# uCurrent.net
KiCad netlist of a schematic drawn in EAGLE
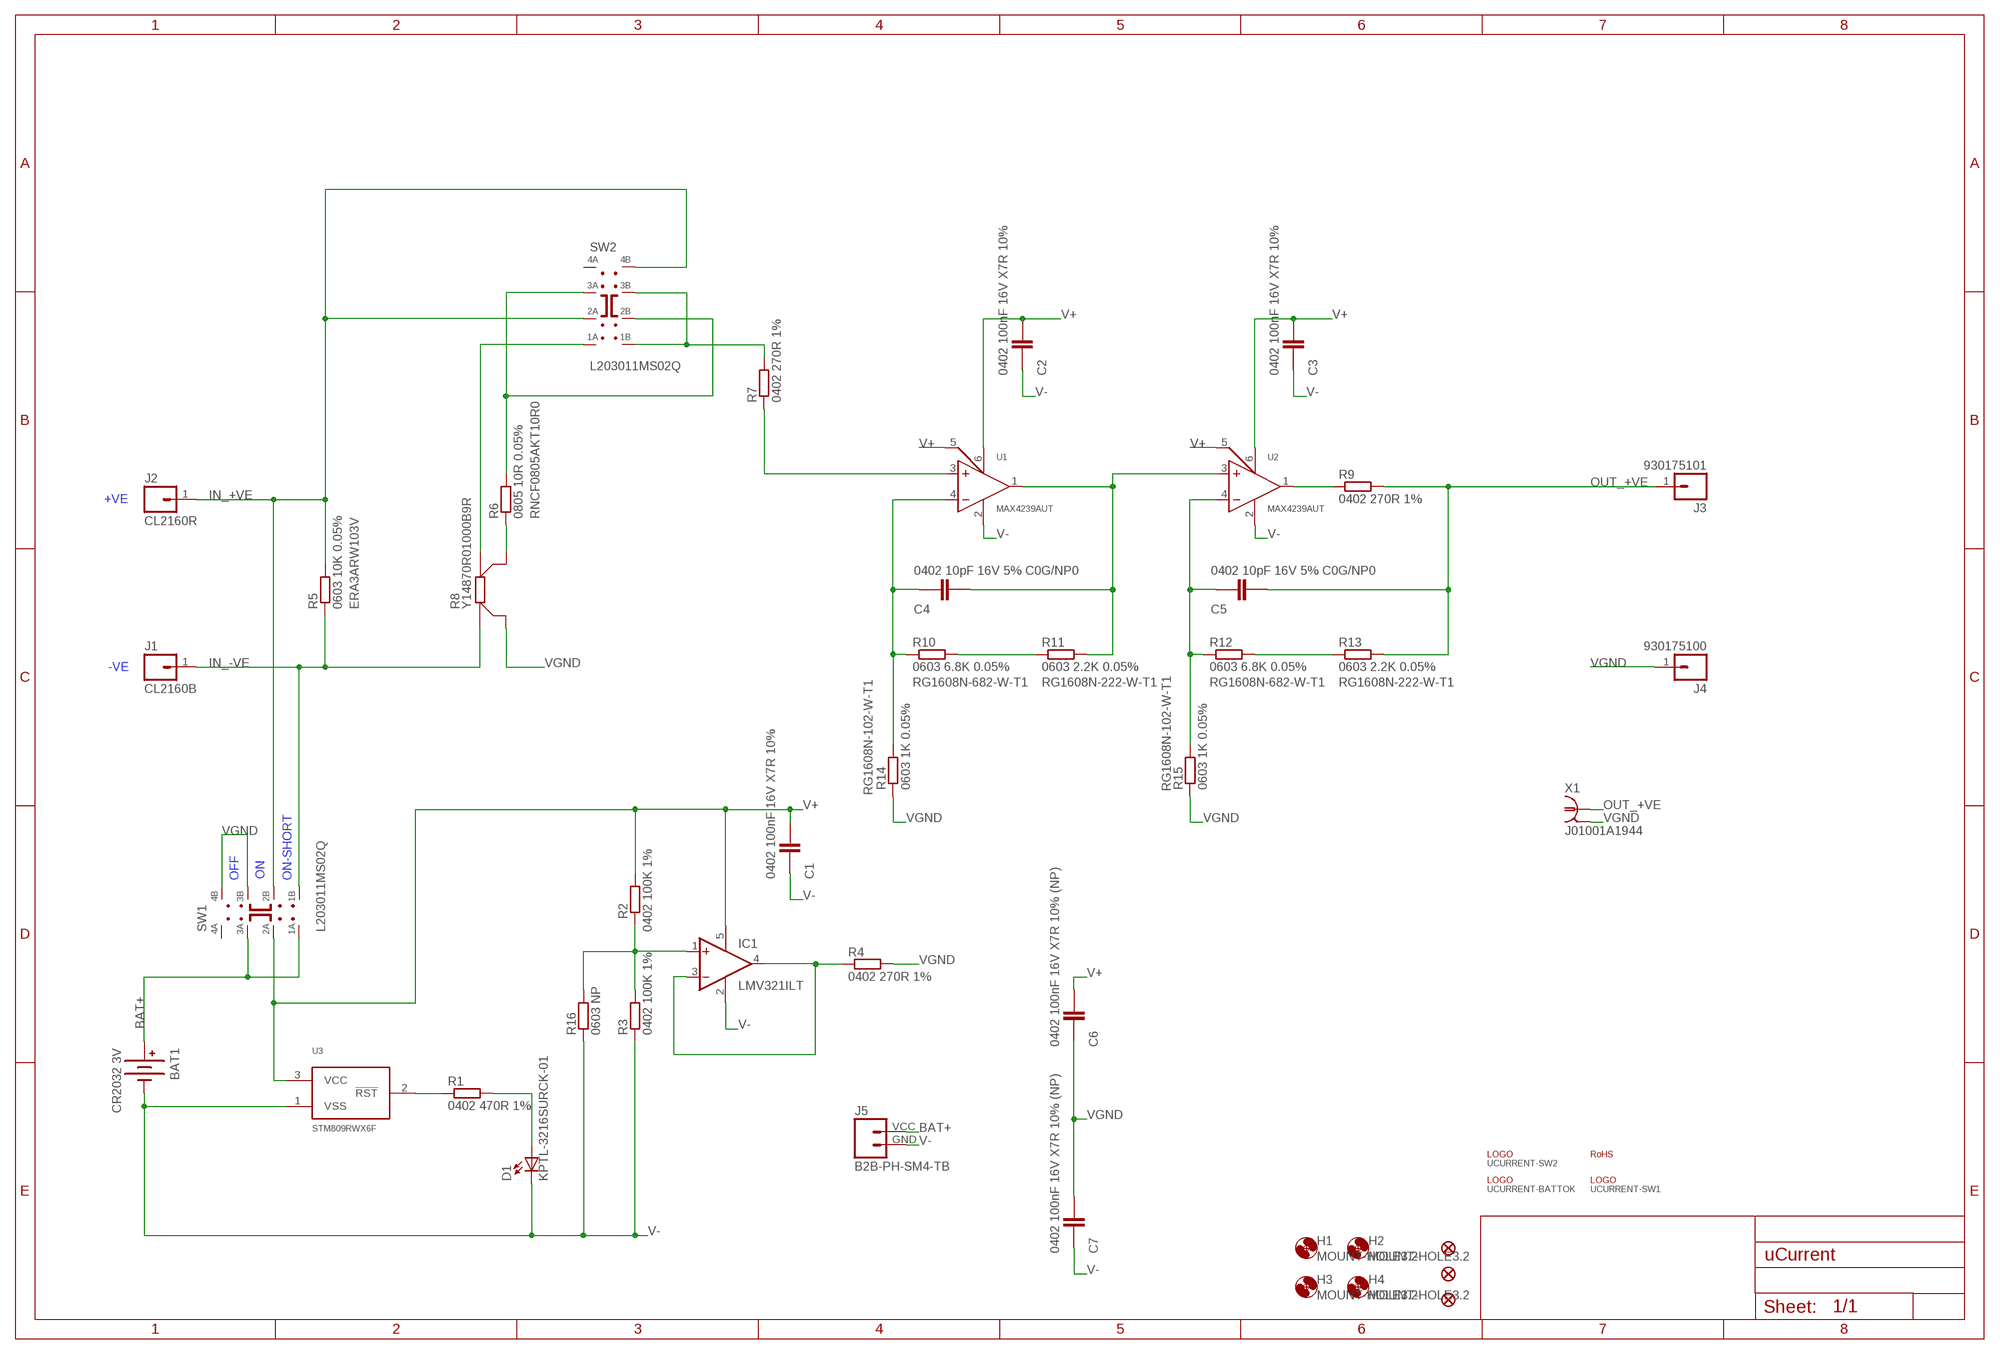
[diagram p0: schematic, sheet 1]

(export (version "E")
  (design (tool "Eeschema 10.0.6"))
  (components
    (comp (ref "BAT1")
      (value "CR2032 3V")
      (footprint "eagle-import:KEYSTONE_1058")
      (libsource (lib "eagle-import") (part "BATTERY-KEYSTONE_1058"))
    )
    (comp (ref "C1")
      (value "0402 100nF 16V X7R 10%")
      (footprint "eagle-import:C0402-SMALLER")
      (libsource (lib "eagle-import") (part "C-EUC0402-SMALLER"))
    )
    (comp (ref "C2")
      (value "0402 100nF 16V X7R 10%")
      (footprint "eagle-import:C0402-SMALLER")
      (libsource (lib "eagle-import") (part "C-EUC0402-SMALLER"))
    )
    (comp (ref "C3")
      (value "0402 100nF 16V X7R 10%")
      (footprint "eagle-import:C0402-SMALLER")
      (libsource (lib "eagle-import") (part "C-EUC0402-SMALLER"))
    )
    (comp (ref "C4")
      (value "0402 10pF 16V 5% C0G/NP0")
      (footprint "eagle-import:C0402-SMALLER")
      (libsource (lib "eagle-import") (part "C-EUC0402-SMALLER"))
    )
    (comp (ref "C5")
      (value "0402 10pF 16V 5% C0G/NP0")
      (footprint "eagle-import:C0402-SMALLER")
      (libsource (lib "eagle-import") (part "C-EUC0402-SMALLER"))
    )
    (comp (ref "C6")
      (value "0402 100nF 16V X7R 10% (NP)")
      (footprint "eagle-import:C0402-SMALLER")
      (libsource (lib "eagle-import") (part "C-EUC0402-SMALLER"))
    )
    (comp (ref "C7")
      (value "0402 100nF 16V X7R 10% (NP)")
      (footprint "eagle-import:C0402-SMALLER")
      (libsource (lib "eagle-import") (part "C-EUC0402-SMALLER"))
    )
    (comp (ref "D1")
      (value "KPTL-3216SURCK-01")
      (footprint "eagle-import:KPTL-3216")
      (libsource (lib "eagle-import") (part "LED-KPTL-3216"))
    )
    (comp (ref "H1")
      (value "MOUNT-HOLE3.2")
      (footprint "eagle-import:3,2")
      (libsource (lib "eagle-import") (part "MOUNT-HOLE3.2"))
    )
    (comp (ref "H2")
      (value "MOUNT-HOLE3.2")
      (footprint "eagle-import:3,2")
      (libsource (lib "eagle-import") (part "MOUNT-HOLE3.2"))
    )
    (comp (ref "H3")
      (value "MOUNT-HOLE3.2")
      (footprint "eagle-import:3,2")
      (libsource (lib "eagle-import") (part "MOUNT-HOLE3.2"))
    )
    (comp (ref "H4")
      (value "MOUNT-HOLE3.2")
      (footprint "eagle-import:3,2")
      (libsource (lib "eagle-import") (part "MOUNT-HOLE3.2"))
    )
    (comp (ref "IC1")
      (value "LMV321ILT")
      (footprint "eagle-import:SOT23-5")
      (libsource (lib "eagle-import") (part "LMV321?M5X"))
    )
    (comp (ref "J1")
      (value "CL2160B")
      (footprint "eagle-import:CL2160R")
      (libsource (lib "eagle-import") (part "M01-CL2160R"))
    )
    (comp (ref "J2")
      (value "CL2160R")
      (footprint "eagle-import:CL2160R")
      (libsource (lib "eagle-import") (part "M01-CL2160R"))
    )
    (comp (ref "J3")
      (value "930175101")
      (footprint "eagle-import:BUG10_SOCKET")
      (libsource (lib "eagle-import") (part "M01-BUG10"))
    )
    (comp (ref "J4")
      (value "930175100")
      (footprint "eagle-import:BUG10_SOCKET")
      (libsource (lib "eagle-import") (part "M01-BUG10"))
    )
    (comp (ref "J5")
      (value "B2B-PH-SM4-TB")
      (footprint "eagle-import:JST-PH-SMD-VERT-02")
      (libsource (lib "eagle-import") (part "M02-JST-PH-SMD-VERT"))
    )
    (comp (ref "JP1")
      (value "FIDUCIAL1X2.5-STOP")
      (footprint "eagle-import:FIDUCIAL-1X2.5-STOP")
      (libsource (lib "eagle-import") (part "FIDUCIAL1X2.5-STOP"))
    )
    (comp (ref "JP2")
      (value "FIDUCIAL1X2.5-STOP")
      (footprint "eagle-import:FIDUCIAL-1X2.5-STOP")
      (libsource (lib "eagle-import") (part "FIDUCIAL1X2.5-STOP"))
    )
    (comp (ref "JP3")
      (value "FIDUCIAL1X2.5-STOP")
      (footprint "eagle-import:FIDUCIAL-1X2.5-STOP")
      (libsource (lib "eagle-import") (part "FIDUCIAL1X2.5-STOP"))
    )
    (comp (ref "L1")
      (value "UCURRENT-BATTOK")
      (footprint "eagle-import:UCURRENT_BATTOK")
      (libsource (lib "eagle-import") (part "UCURRENT-BATTOK"))
    )
    (comp (ref "L2")
      (value "UCURRENT-SW1")
      (footprint "eagle-import:UCURRENT_SW1")
      (libsource (lib "eagle-import") (part "UCURRENT-SW1"))
    )
    (comp (ref "L3")
      (value "UCURRENT-SW2")
      (footprint "eagle-import:UCURRENT_SW2")
      (libsource (lib "eagle-import") (part "UCURRENT-SW2"))
    )
    (comp (ref "R1")
      (value "0402 470R 1%")
      (footprint "eagle-import:R0402-SMALLER")
      (libsource (lib "eagle-import") (part "R-EU_R0402-SMALLER"))
    )
    (comp (ref "R2")
      (value "0402 100K 1%")
      (footprint "eagle-import:R0402-SMALLER")
      (libsource (lib "eagle-import") (part "R-EU_R0402-SMALLER"))
    )
    (comp (ref "R3")
      (value "0402 100K 1%")
      (footprint "eagle-import:R0402-SMALLER")
      (libsource (lib "eagle-import") (part "R-EU_R0402-SMALLER"))
    )
    (comp (ref "R4")
      (value "0402 270R 1%")
      (footprint "eagle-import:R0402-SMALLER")
      (libsource (lib "eagle-import") (part "R-EU_R0402-SMALLER"))
    )
    (comp (ref "R5")
      (value "0603 10K 0.05%")
      (footprint "eagle-import:C0603K-SMALL")
      (fields (field (name "MPN") "ERA3ARW103V"))
      (libsource (lib "eagle-import") (part "R-EU_0603K-SMALL"))
    )
    (comp (ref "R6")
      (value "0805 10R 0.05%")
      (footprint "eagle-import:R0805")
      (fields (field (name "MPN") "RNCF0805AKT10R0"))
      (libsource (lib "eagle-import") (part "R-EU_R0805"))
    )
    (comp (ref "R7")
      (value "0402 270R 1%")
      (footprint "eagle-import:R0402-SMALLER")
      (libsource (lib "eagle-import") (part "R-EU_R0402-SMALLER"))
    )
    (comp (ref "R8")
      (value "Y14870R01000B9R")
      (footprint "eagle-import:CSM2512-L")
      (libsource (lib "eagle-import") (part "R-EU_KELVIN_Y14870R01000B9R"))
    )
    (comp (ref "R9")
      (value "0402 270R 1%")
      (footprint "eagle-import:R0402-SMALLER")
      (libsource (lib "eagle-import") (part "R-EU_R0402-SMALLER"))
    )
    (comp (ref "R10")
      (value "0603 6.8K 0.05%")
      (footprint "eagle-import:C0603K-SMALL")
      (fields (field (name "MPN") "RG1608N-682-W-T1"))
      (libsource (lib "eagle-import") (part "R-EU_0603K-SMALL"))
    )
    (comp (ref "R11")
      (value "0603 2.2K 0.05%")
      (footprint "eagle-import:C0603K-SMALL")
      (fields (field (name "MPN") "RG1608N-222-W-T1"))
      (libsource (lib "eagle-import") (part "R-EU_0603K-SMALL"))
    )
    (comp (ref "R12")
      (value "0603 6.8K 0.05%")
      (footprint "eagle-import:C0603K-SMALL")
      (fields (field (name "MPN") "RG1608N-682-W-T1"))
      (libsource (lib "eagle-import") (part "R-EU_0603K-SMALL"))
    )
    (comp (ref "R13")
      (value "0603 2.2K 0.05%")
      (footprint "eagle-import:C0603K-SMALL")
      (fields (field (name "MPN") "RG1608N-222-W-T1"))
      (libsource (lib "eagle-import") (part "R-EU_0603K-SMALL"))
    )
    (comp (ref "R14")
      (value "0603 1K 0.05%")
      (footprint "eagle-import:C0603K-SMALL")
      (fields (field (name "MPN") "RG1608N-102-W-T1"))
      (libsource (lib "eagle-import") (part "R-EU_0603K-SMALL"))
    )
    (comp (ref "R15")
      (value "0603 1K 0.05%")
      (footprint "eagle-import:C0603K-SMALL")
      (fields (field (name "MPN") "RG1608N-102-W-T1"))
      (libsource (lib "eagle-import") (part "R-EU_0603K-SMALL"))
    )
    (comp (ref "R16")
      (value "0603 NP")
      (footprint "eagle-import:C0603K-SMALL")
      (libsource (lib "eagle-import") (part "R-EU_0603K-SMALL"))
    )
    (comp (ref "SW1")
      (value "L203011MS02Q")
      (footprint "eagle-import:L203011MS02Q")
      (libsource (lib "eagle-import") (part "SWITCH-DP3T-L203011MS02Q"))
    )
    (comp (ref "SW2")
      (value "L203011MS02Q")
      (footprint "eagle-import:L203011MS02Q")
      (libsource (lib "eagle-import") (part "SWITCH-DP3T-L203011MS02Q"))
    )
    (comp (ref "U$1")
      (value "ROHS-1MM")
      (footprint "eagle-import:ROHS-1MM")
      (libsource (lib "eagle-import") (part "ROHS-1MM"))
    )
    (comp (ref "U1")
      (value "MAX4239AUT")
      (footprint "eagle-import:SOT-23-6")
      (libsource (lib "eagle-import") (part "MAX4239"))
    )
    (comp (ref "U2")
      (value "MAX4239AUT")
      (footprint "eagle-import:SOT-23-6")
      (libsource (lib "eagle-import") (part "MAX4239"))
    )
    (comp (ref "U3")
      (value "STM809RWX6F")
      (footprint "eagle-import:SOT23-3")
      (libsource (lib "eagle-import") (part "STM809RWX6F"))
    )
    (comp (ref "X1")
      (value "J01001A1944")
      (footprint "eagle-import:J01001A1944")
      (libsource (lib "eagle-import") (part "BNC_J01001A1944"))
    )
  )
  (nets
    (net (code "1") (name "/BAT+") (class "Default")
      (node (ref "BAT1") (pin "+VE") (pinfunction "+_+VE") (pintype "power_in"))
      (node (ref "J5") (pin "VCC") (pinfunction "2_VCC") (pintype "passive"))
      (node (ref "SW1") (pin "1") (pinfunction "1_1") (pintype "bidirectional"))
      (node (ref "SW1") (pin "3") (pinfunction "3_3") (pintype "bidirectional"))
    )
    (net (code "2") (name "/IN_+VE") (class "Default")
      (node (ref "J2") (pin "1") (pinfunction "1_1") (pintype "passive"))
      (node (ref "R5") (pin "2") (pinfunction "2_2") (pintype "passive"))
      (node (ref "SW1") (pin "6") (pinfunction "6_6") (pintype "bidirectional"))
      (node (ref "SW2") (pin "2") (pinfunction "2_2") (pintype "bidirectional"))
      (node (ref "SW2") (pin "8") (pinfunction "8_8") (pintype "bidirectional"))
    )
    (net (code "3") (name "/IN_-VE") (class "Default")
      (node (ref "J1") (pin "1") (pinfunction "1_1") (pintype "passive"))
      (node (ref "R5") (pin "1") (pinfunction "1_1") (pintype "passive"))
      (node (ref "R8") (pin "I1") (pinfunction "A_I1") (pintype "passive"))
      (node (ref "SW1") (pin "5") (pinfunction "5_5") (pintype "bidirectional"))
    )
    (net (code "4") (name "/OUT_+VE") (class "Default")
      (node (ref "C5") (pin "1") (pinfunction "1_1") (pintype "passive"))
      (node (ref "J3") (pin "1") (pinfunction "1_1") (pintype "passive"))
      (node (ref "R13") (pin "2") (pinfunction "2_2") (pintype "passive"))
      (node (ref "R9") (pin "2") (pinfunction "2_2") (pintype "passive"))
      (node (ref "X1") (pin "1") (pinfunction "1_1") (pintype "passive"))
    )
    (net (code "5") (name "/V+") (class "Default")
      (node (ref "C1") (pin "1") (pinfunction "1_1") (pintype "passive"))
      (node (ref "C2") (pin "1") (pinfunction "1_1") (pintype "passive"))
      (node (ref "C3") (pin "1") (pinfunction "1_1") (pintype "passive"))
      (node (ref "C6") (pin "1") (pinfunction "1_1") (pintype "passive"))
      (node (ref "IC1") (pin "5") (pinfunction "V+_5") (pintype "power_in"))
      (node (ref "R2") (pin "2") (pinfunction "2_2") (pintype "passive"))
      (node (ref "SW1") (pin "2") (pinfunction "2_2") (pintype "bidirectional"))
      (node (ref "U1") (pin "5") (pinfunction "5_5") (pintype "bidirectional"))
      (node (ref "U1") (pin "6") (pinfunction "6_6") (pintype "bidirectional"))
      (node (ref "U2") (pin "5") (pinfunction "5_5") (pintype "bidirectional"))
      (node (ref "U2") (pin "6") (pinfunction "6_6") (pintype "bidirectional"))
      (node (ref "U3") (pin "3") (pinfunction "VCC_3") (pintype "bidirectional"))
    )
    (net (code "6") (name "/V-") (class "Default")
      (node (ref "BAT1") (pin "-VE") (pinfunction "-_-VE") (pintype "power_in"))
      (node (ref "C1") (pin "2") (pinfunction "2_2") (pintype "passive"))
      (node (ref "C2") (pin "2") (pinfunction "2_2") (pintype "passive"))
      (node (ref "C3") (pin "2") (pinfunction "2_2") (pintype "passive"))
      (node (ref "C7") (pin "2") (pinfunction "2_2") (pintype "passive"))
      (node (ref "D1") (pin "C") (pinfunction "C_C") (pintype "passive"))
      (node (ref "IC1") (pin "2") (pinfunction "V-_2") (pintype "power_in"))
      (node (ref "J5") (pin "GND") (pinfunction "1_GND") (pintype "passive"))
      (node (ref "R16") (pin "1") (pinfunction "1_1") (pintype "passive"))
      (node (ref "R3") (pin "1") (pinfunction "1_1") (pintype "passive"))
      (node (ref "U1") (pin "2") (pinfunction "2_2") (pintype "bidirectional"))
      (node (ref "U2") (pin "2") (pinfunction "2_2") (pintype "bidirectional"))
      (node (ref "U3") (pin "1") (pinfunction "VSS_1") (pintype "bidirectional"))
    )
    (net (code "7") (name "/VGND") (class "Default")
      (node (ref "C6") (pin "2") (pinfunction "2_2") (pintype "passive"))
      (node (ref "C7") (pin "1") (pinfunction "1_1") (pintype "passive"))
      (node (ref "J4") (pin "1") (pinfunction "1_1") (pintype "passive"))
      (node (ref "R14") (pin "1") (pinfunction "1_1") (pintype "passive"))
      (node (ref "R15") (pin "1") (pinfunction "1_1") (pintype "passive"))
      (node (ref "R4") (pin "2") (pinfunction "2_2") (pintype "passive"))
      (node (ref "R8") (pin "E1") (pinfunction "B_E1") (pintype "passive"))
      (node (ref "SW1") (pin "7") (pinfunction "7_7") (pintype "bidirectional"))
      (node (ref "SW1") (pin "8") (pinfunction "8_8") (pintype "bidirectional"))
      (node (ref "X1") (pin "2") (pinfunction "2_2") (pintype "passive"))
      (node (ref "X1") (pin "3") (pinfunction "2_3") (pintype "passive"))
      (node (ref "X1") (pin "4") (pinfunction "2_4") (pintype "passive"))
      (node (ref "X1") (pin "5") (pinfunction "2_5") (pintype "passive"))
    )
    (net (code "8") (name "Net-(C4-Pad1)") (class "Default")
      (node (ref "C4") (pin "1") (pinfunction "1_1") (pintype "passive"))
      (node (ref "R11") (pin "2") (pinfunction "2_2") (pintype "passive"))
      (node (ref "U1") (pin "1") (pinfunction "1_1") (pintype "bidirectional"))
      (node (ref "U2") (pin "3") (pinfunction "3_3") (pintype "bidirectional"))
    )
    (net (code "9") (name "Net-(C4-Pad2)") (class "Default")
      (node (ref "C4") (pin "2") (pinfunction "2_2") (pintype "passive"))
      (node (ref "R10") (pin "1") (pinfunction "1_1") (pintype "passive"))
      (node (ref "R14") (pin "2") (pinfunction "2_2") (pintype "passive"))
      (node (ref "U1") (pin "4") (pinfunction "4_4") (pintype "bidirectional"))
    )
    (net (code "10") (name "Net-(C5-Pad2)") (class "Default")
      (node (ref "C5") (pin "2") (pinfunction "2_2") (pintype "passive"))
      (node (ref "R12") (pin "1") (pinfunction "1_1") (pintype "passive"))
      (node (ref "R15") (pin "2") (pinfunction "2_2") (pintype "passive"))
      (node (ref "U2") (pin "4") (pinfunction "4_4") (pintype "bidirectional"))
    )
    (net (code "11") (name "Net-(D1-PadA)") (class "Default")
      (node (ref "D1") (pin "A") (pinfunction "A_A") (pintype "passive"))
      (node (ref "R1") (pin "2") (pinfunction "2_2") (pintype "passive"))
    )
    (net (code "12") (name "Net-(IC1-+IN)") (class "Default")
      (node (ref "IC1") (pin "1") (pinfunction "+IN_1") (pintype "input"))
      (node (ref "R16") (pin "2") (pinfunction "2_2") (pintype "passive"))
      (node (ref "R2") (pin "1") (pinfunction "1_1") (pintype "passive"))
      (node (ref "R3") (pin "2") (pinfunction "2_2") (pintype "passive"))
    )
    (net (code "13") (name "Net-(IC1--IN)") (class "Default")
      (node (ref "IC1") (pin "3") (pinfunction "-IN_3") (pintype "input"))
      (node (ref "IC1") (pin "4") (pinfunction "OUT_4") (pintype "output"))
      (node (ref "R4") (pin "1") (pinfunction "1_1") (pintype "passive"))
    )
    (net (code "14") (name "Net-(R6-Pad2)") (class "Default")
      (node (ref "R6") (pin "2") (pinfunction "2_2") (pintype "passive"))
      (node (ref "SW2") (pin "3") (pinfunction "3_3") (pintype "bidirectional"))
      (node (ref "SW2") (pin "6") (pinfunction "6_6") (pintype "bidirectional"))
    )
    (net (code "15") (name "Net-(R7-Pad1)") (class "Default")
      (node (ref "R7") (pin "1") (pinfunction "1_1") (pintype "passive"))
      (node (ref "U1") (pin "3") (pinfunction "3_3") (pintype "bidirectional"))
    )
    (net (code "16") (name "Net-(R7-Pad2)") (class "Default")
      (node (ref "R7") (pin "2") (pinfunction "2_2") (pintype "passive"))
      (node (ref "SW2") (pin "5") (pinfunction "5_5") (pintype "bidirectional"))
      (node (ref "SW2") (pin "7") (pinfunction "7_7") (pintype "bidirectional"))
    )
    (net (code "17") (name "Net-(R8-C)") (class "Default")
      (node (ref "R6") (pin "1") (pinfunction "1_1") (pintype "passive"))
      (node (ref "R8") (pin "E2") (pinfunction "C_E2") (pintype "bidirectional"))
    )
    (net (code "18") (name "Net-(R8-D)") (class "Default")
      (node (ref "R8") (pin "I2") (pinfunction "D_I2") (pintype "passive"))
      (node (ref "SW2") (pin "1") (pinfunction "1_1") (pintype "bidirectional"))
    )
    (net (code "19") (name "Net-(R9-Pad1)") (class "Default")
      (node (ref "R9") (pin "1") (pinfunction "1_1") (pintype "passive"))
      (node (ref "U2") (pin "1") (pinfunction "1_1") (pintype "bidirectional"))
    )
    (net (code "20") (name "Net-(R10-Pad2)") (class "Default")
      (node (ref "R10") (pin "2") (pinfunction "2_2") (pintype "passive"))
      (node (ref "R11") (pin "1") (pinfunction "1_1") (pintype "passive"))
    )
    (net (code "21") (name "Net-(R12-Pad2)") (class "Default")
      (node (ref "R12") (pin "2") (pinfunction "2_2") (pintype "passive"))
      (node (ref "R13") (pin "1") (pinfunction "1_1") (pintype "passive"))
    )
    (net (code "22") (name "Net-(U3-~{RST})") (class "Default")
      (node (ref "R1") (pin "1") (pinfunction "1_1") (pintype "passive"))
      (node (ref "U3") (pin "2") (pinfunction "~{RST}_2") (pintype "bidirectional"))
    )
    (net (code "23") (name "unconnected-(SW1-Pad4)") (class "Default")
      (node (ref "SW1") (pin "4") (pinfunction "4_4") (pintype "bidirectional"))
    )
    (net (code "24") (name "unconnected-(SW2-Pad4)") (class "Default")
      (node (ref "SW2") (pin "4") (pinfunction "4_4") (pintype "bidirectional"))
    )
  )
)
